# Sheet1.net
KiCad netlist of a schematic drawn in Altium Designer
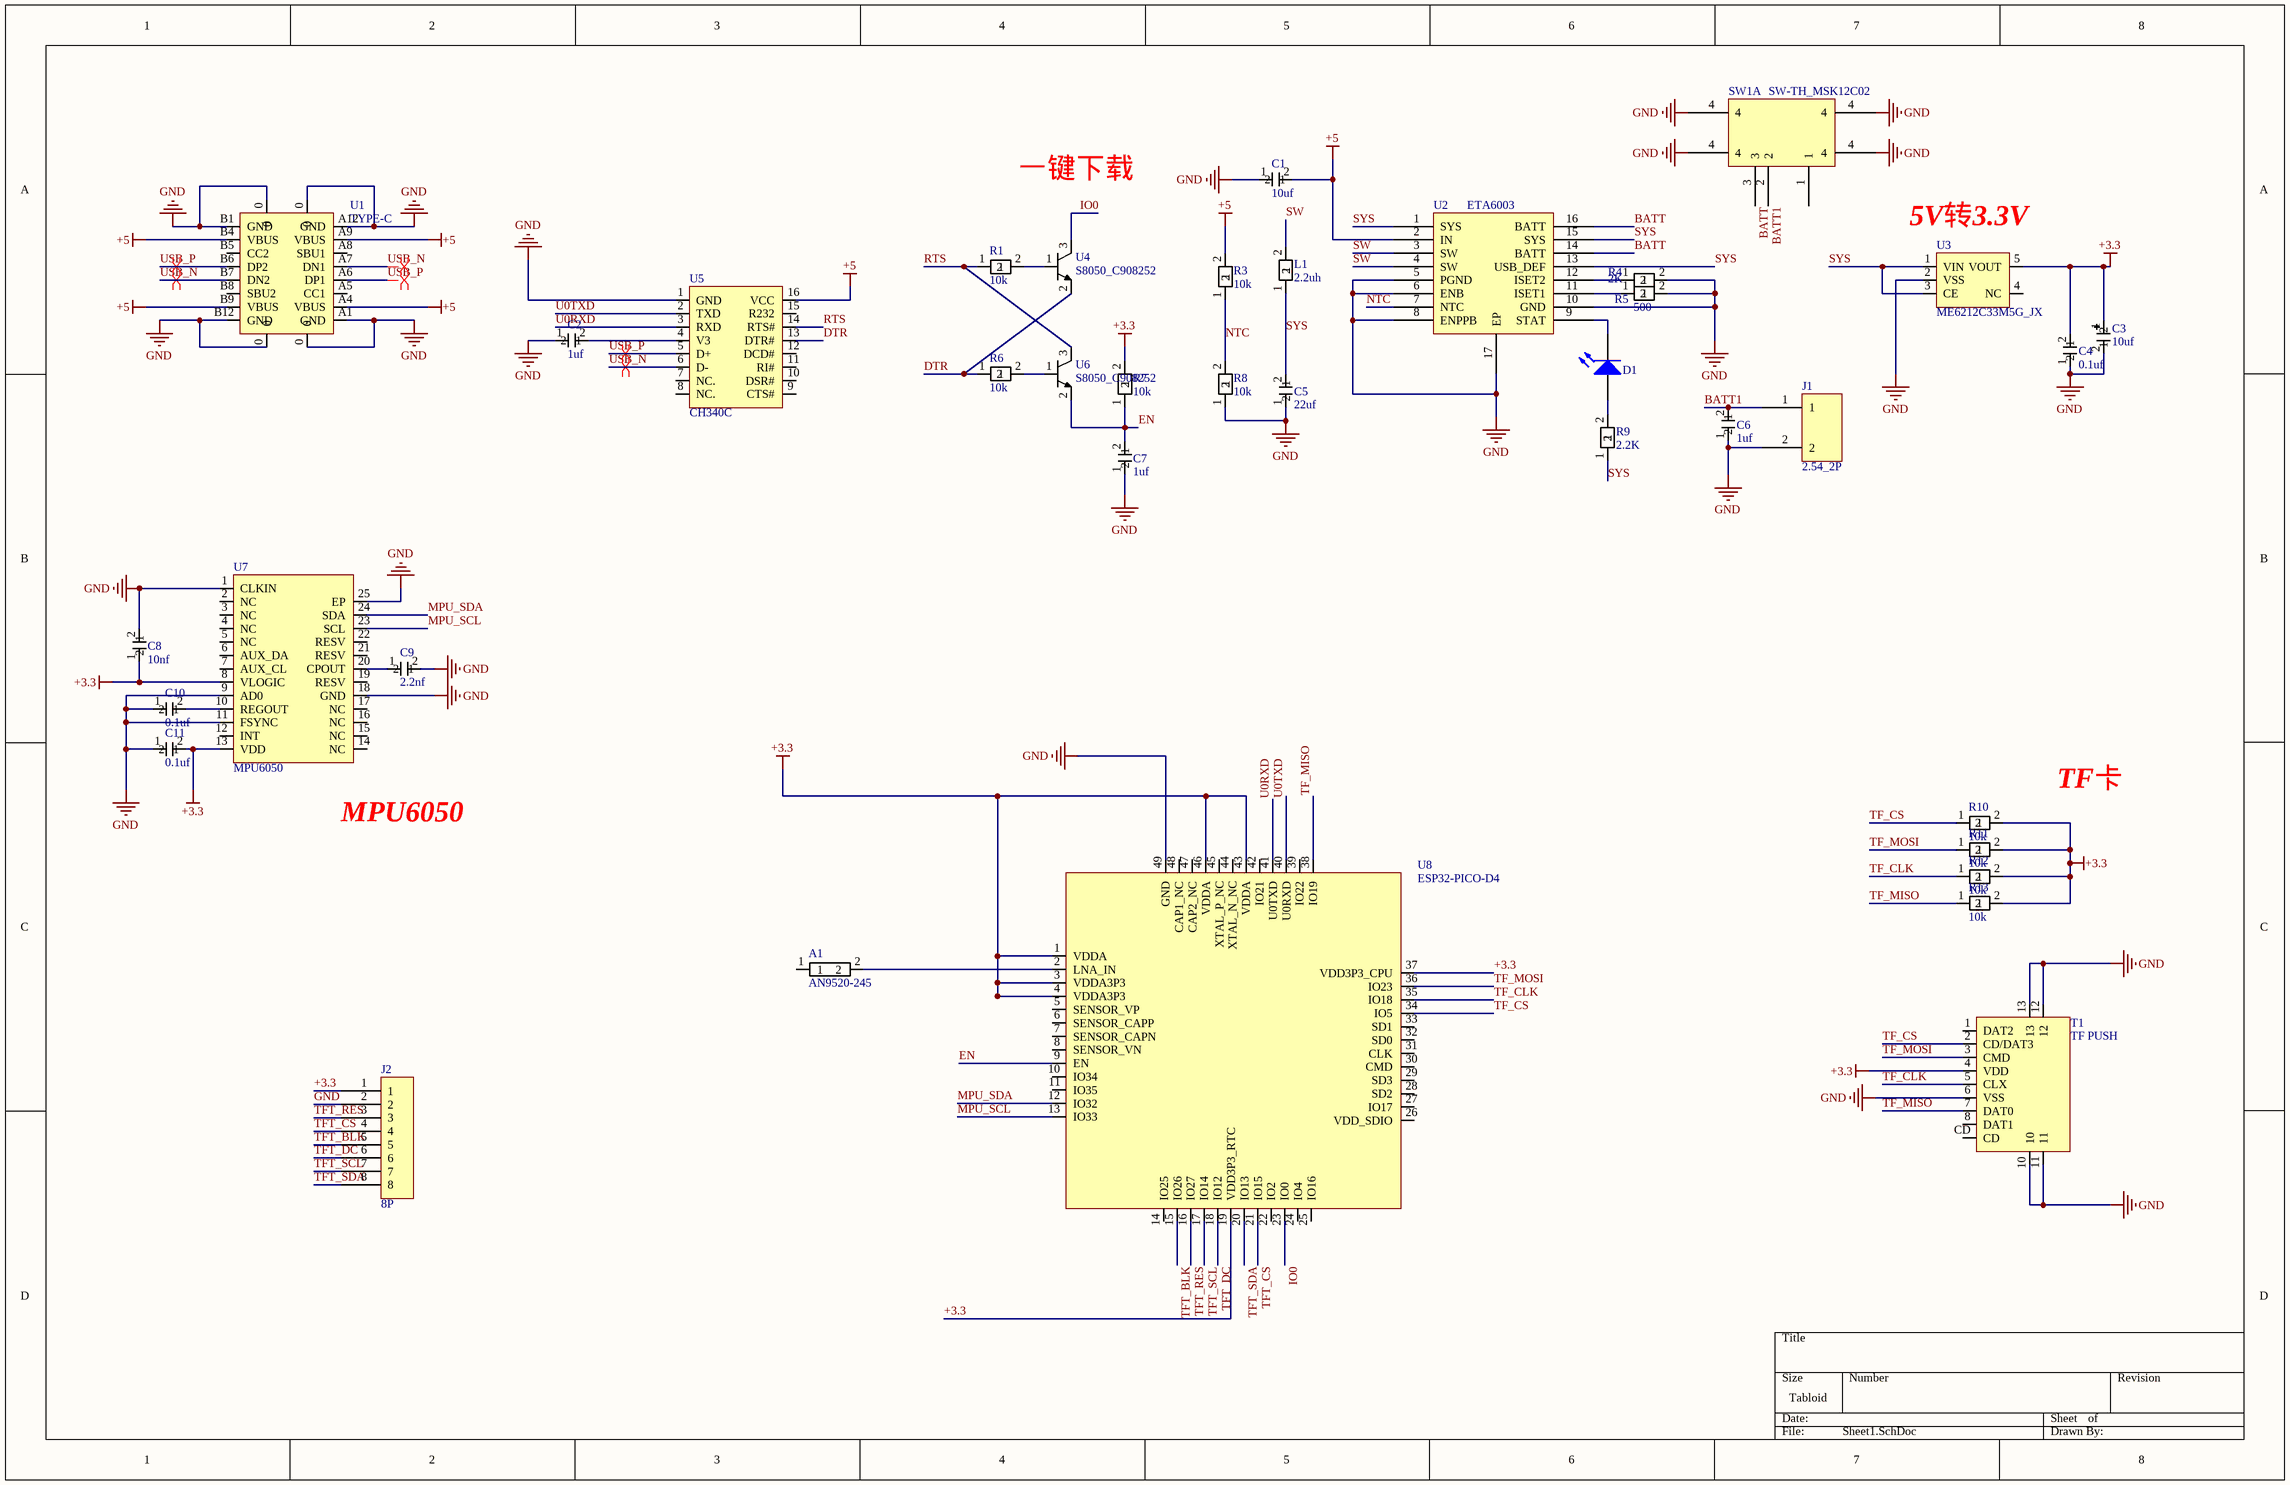
[diagram p0: Sheet1.SchDoc]

(export (version "E")
  (design (tool "Eeschema 10.0.6"))
  (components
    (comp (ref "A1") (value "AN9520-245") (footprint "AN9520-245") (libsource (lib "My") (part "AN9520-245")))
    (comp (ref "C1") (value "10uf") (footprint "C0805") (libsource (lib "My") (part "C0805")))
    (comp (ref "C2") (value "1uf") (footprint "C0805") (libsource (lib "My") (part "C0805")))
    (comp (ref "C3") (value "10uf") (footprint "C+") (libsource (lib "My") (part "C+")))
    (comp (ref "C4") (value "0.1uf") (footprint "C0805") (libsource (lib "My") (part "C0805")))
    (comp (ref "C5") (value "22uf") (footprint "C0805") (libsource (lib "My") (part "C0805")))
    (comp (ref "C6") (value "1uf") (footprint "C0805") (libsource (lib "My") (part "C0805")))
    (comp (ref "C7") (value "1uf") (footprint "C0805") (libsource (lib "My") (part "C0805")))
    (comp (ref "C8") (value "10nf") (footprint "C0805") (libsource (lib "My") (part "C0805")))
    (comp (ref "C9") (value "2.2nf") (footprint "C0805") (libsource (lib "My") (part "C0805")))
    (comp (ref "C10") (value "0.1uf") (footprint "C0805") (libsource (lib "My") (part "C0805")))
    (comp (ref "C11") (value "0.1uf") (footprint "C0805") (libsource (lib "My") (part "C0805")))
    (comp (ref "D1")
      (value "LED 蓝 0805")
      (footprint "LED 蓝  0805")
      (libsource (lib "改好的库") (part "LED 蓝 0805"))
    )
    (comp (ref "J1") (value "2.54_2P") (footprint "2P") (libsource (lib "My") (part "2.54_2P")))
    (comp (ref "J2") (value "8P") (footprint "8P-P2.54") (libsource (lib "My") (part "8P")))
    (comp (ref "L1") (value "2.2uh") (footprint "R0805") (libsource (lib "My") (part "R0805")))
    (comp (ref "R1") (value "10k") (footprint "R0805") (libsource (lib "Schlib1") (part "R0805")))
    (comp (ref "R3") (value "10k") (footprint "R0805") (libsource (lib "My") (part "R0805")))
    (comp (ref "R4") (value "2K") (footprint "R0805") (libsource (lib "My") (part "R0805")))
    (comp (ref "R5") (value "500") (footprint "R0805") (libsource (lib "My") (part "R0805")))
    (comp (ref "R6") (value "10k") (footprint "R0805") (libsource (lib "Schlib1") (part "R0805")))
    (comp (ref "R7") (value "10k") (footprint "R0805") (libsource (lib "Schlib1") (part "R0805")))
    (comp (ref "R8") (value "10k") (footprint "R0805") (libsource (lib "My") (part "R0805")))
    (comp (ref "R9") (value "2.2K") (footprint "R0805") (libsource (lib "My") (part "R0805")))
    (comp (ref "R10") (value "10k") (footprint "R0805") (libsource (lib "Schlib1") (part "R0805")))
    (comp (ref "R11") (value "10k") (footprint "R0805") (libsource (lib "Schlib1") (part "R0805")))
    (comp (ref "R12") (value "10k") (footprint "R0805") (libsource (lib "Schlib1") (part "R0805")))
    (comp (ref "R13") (value "10k") (footprint "R0805") (libsource (lib "Schlib1") (part "R0805")))
    (comp (ref "SW1")
      (value "SW-TH_MSK12C02")
      (footprint "SW-TH_MSK12C02")
      (libsource (lib "My") (part "SW-TH_MSK12C02"))
    )
    (comp (ref "T1") (value "TF PUSH") (footprint "TF-SMD_TF-PUSH") (libsource (lib "My") (part "TF PUSH")))
    (comp (ref "U1")
      (value "TYPE-C")
      (footprint "USB-C")
      (description "TYPE-C-31-M-12")
      (libsource (lib "My") (part "TYPE-C"))
    )
    (comp (ref "U2") (value "ETA6003") (footprint "ETA6003") (libsource (lib "My") (part "ETA6003")))
    (comp (ref "U3")
      (value "ME6212C33M5G_JX")
      (footprint "ME6212C33M5G_JX")
      (libsource (lib "My") (part "ME6212C33M5G_JX"))
    )
    (comp (ref "U4") (value "S8050_C908252") (footprint "s8050") (libsource (lib "My") (part "s8050")))
    (comp (ref "U5") (value "CH340C") (footprint "CH340C") (libsource (lib "My") (part "CH340C")))
    (comp (ref "U6") (value "S8050_C908252") (footprint "s8050") (libsource (lib "My") (part "s8050")))
    (comp (ref "U7") (value "MPU6050") (footprint "MPU6050") (libsource (lib "My") (part "MPU6050")))
    (comp (ref "U8")
      (value "ESP32-PICO-D4")
      (footprint "ESP32-PICO-D4")
      (libsource (lib "My") (part "ESP32-PICO-D4"))
    )
  )
  (nets
    (net (code "1") (name "+3.3") (class "Default")
      (node (ref "C11") (pin "2") (pinfunction "2_2") (pintype "passive"))
      (node (ref "C3") (pin "1") (pinfunction "1_1") (pintype "passive"))
      (node (ref "C4") (pin "2") (pinfunction "2_2") (pintype "passive"))
      (node (ref "C8") (pin "1") (pinfunction "1_1") (pintype "passive"))
      (node (ref "J2") (pin "1") (pinfunction "1_1") (pintype "passive"))
      (node (ref "R10") (pin "2") (pinfunction "2_2") (pintype "passive"))
      (node (ref "R11") (pin "2") (pinfunction "2_2") (pintype "passive"))
      (node (ref "R12") (pin "2") (pinfunction "2_2") (pintype "passive"))
      (node (ref "R13") (pin "2") (pinfunction "2_2") (pintype "passive"))
      (node (ref "R7") (pin "2") (pinfunction "2_2") (pintype "passive"))
      (node (ref "T1") (pin "4") (pinfunction "VDD_4") (pintype "passive"))
      (node (ref "U3") (pin "5") (pinfunction "VOUT_5") (pintype "passive"))
      (node (ref "U7") (pin "13") (pinfunction "VDD_13") (pintype "passive"))
      (node (ref "U7") (pin "8") (pinfunction "VLOGIC_8") (pintype "passive"))
      (node (ref "U8") (pin "1") (pinfunction "VDDA_1") (pintype "passive"))
      (node (ref "U8") (pin "19") (pinfunction "VDD3P3_RTC_19") (pintype "passive"))
      (node (ref "U8") (pin "3") (pinfunction "VDDA3P3_3") (pintype "passive"))
      (node (ref "U8") (pin "37") (pinfunction "VDD3P3_CPU_37") (pintype "passive"))
      (node (ref "U8") (pin "4") (pinfunction "VDDA3P3_4") (pintype "passive"))
      (node (ref "U8") (pin "43") (pinfunction "VDDA_43") (pintype "passive"))
      (node (ref "U8") (pin "46") (pinfunction "VDDA_46") (pintype "passive"))
    )
    (net (code "2") (name "+5") (class "Default")
      (node (ref "C1") (pin "2") (pinfunction "2_2") (pintype "passive"))
      (node (ref "R3") (pin "2") (pinfunction "2_2") (pintype "passive"))
      (node (ref "U1") (pin "A4") (pinfunction "VBUS_A4") (pintype "passive"))
      (node (ref "U1") (pin "A9") (pinfunction "VBUS_A9") (pintype "passive"))
      (node (ref "U1") (pin "B4") (pinfunction "VBUS_B4") (pintype "passive"))
      (node (ref "U1") (pin "B9") (pinfunction "VBUS_B9") (pintype "passive"))
      (node (ref "U2") (pin "2") (pinfunction "IN_2") (pintype "passive"))
      (node (ref "U5") (pin "16") (pinfunction "VCC_16") (pintype "passive"))
    )
    (net (code "4") (name "/BATT") (class "Default")
      (node (ref "SW1") (pin "3") (pinfunction "3_3") (pintype "passive"))
      (node (ref "U2") (pin "14") (pinfunction "BATT_14") (pintype "passive"))
      (node (ref "U2") (pin "16") (pinfunction "BATT_16") (pintype "passive"))
    )
    (net (code "5") (name "/BATT1") (class "Default")
      (node (ref "C6") (pin "2") (pinfunction "2_2") (pintype "passive"))
      (node (ref "J1") (pin "1") (pinfunction "1_1") (pintype "passive"))
      (node (ref "SW1") (pin "2") (pinfunction "2_2") (pintype "passive"))
    )
    (net (code "6") (name "/DTR") (class "Default")
      (node (ref "R6") (pin "1") (pinfunction "1_1") (pintype "passive"))
      (node (ref "U4") (pin "2") (pinfunction "E_2") (pintype "passive"))
      (node (ref "U5") (pin "13") (pinfunction "DTR#_13") (pintype "passive"))
    )
    (net (code "7") (name "/EN") (class "Default")
      (node (ref "C7") (pin "2") (pinfunction "2_2") (pintype "passive"))
      (node (ref "R7") (pin "1") (pinfunction "1_1") (pintype "passive"))
      (node (ref "U6") (pin "2") (pinfunction "E_2") (pintype "passive"))
      (node (ref "U8") (pin "9") (pinfunction "EN_9") (pintype "passive"))
    )
    (net (code "8") (name "/IO0") (class "Default")
      (node (ref "U4") (pin "3") (pinfunction "C_3") (pintype "passive"))
      (node (ref "U8") (pin "23") (pinfunction "IO0_23") (pintype "passive"))
    )
    (net (code "9") (name "/MPU_SCL") (class "Default")
      (node (ref "U7") (pin "23") (pinfunction "SCL_23") (pintype "passive"))
      (node (ref "U8") (pin "13") (pinfunction "IO33_13") (pintype "passive"))
    )
    (net (code "10") (name "/MPU_SDA") (class "Default")
      (node (ref "U7") (pin "24") (pinfunction "SDA_24") (pintype "passive"))
      (node (ref "U8") (pin "12") (pinfunction "IO32_12") (pintype "passive"))
    )
    (net (code "11") (name "/NTC") (class "Default")
      (node (ref "R3") (pin "1") (pinfunction "1_1") (pintype "passive"))
      (node (ref "R8") (pin "2") (pinfunction "2_2") (pintype "passive"))
      (node (ref "U2") (pin "7") (pinfunction "NTC_7") (pintype "passive"))
    )
    (net (code "12") (name "/RTS") (class "Default")
      (node (ref "R1") (pin "1") (pinfunction "1_1") (pintype "passive"))
      (node (ref "U5") (pin "14") (pinfunction "RTS#_14") (pintype "passive"))
      (node (ref "U6") (pin "3") (pinfunction "C_3") (pintype "passive"))
    )
    (net (code "13") (name "/SW") (class "Default")
      (node (ref "L1") (pin "2") (pinfunction "2_2") (pintype "passive"))
      (node (ref "U2") (pin "3") (pinfunction "SW_3") (pintype "passive"))
      (node (ref "U2") (pin "4") (pinfunction "SW_4") (pintype "passive"))
    )
    (net (code "14") (name "/SYS") (class "Default")
      (node (ref "C5") (pin "2") (pinfunction "2_2") (pintype "passive"))
      (node (ref "L1") (pin "1") (pinfunction "1_1") (pintype "passive"))
      (node (ref "R9") (pin "1") (pinfunction "1_1") (pintype "passive"))
      (node (ref "U2") (pin "1") (pinfunction "SYS_1") (pintype "passive"))
      (node (ref "U2") (pin "13") (pinfunction "USB_DEF_13") (pintype "passive"))
      (node (ref "U2") (pin "15") (pinfunction "SYS_15") (pintype "passive"))
      (node (ref "U3") (pin "1") (pinfunction "VIN_1") (pintype "passive"))
      (node (ref "U3") (pin "3") (pinfunction "CE_3") (pintype "passive"))
    )
    (net (code "15") (name "/TFT_BLK") (class "Default")
      (node (ref "J2") (pin "5") (pinfunction "5_5") (pintype "passive"))
      (node (ref "U8") (pin "15") (pinfunction "IO26_15") (pintype "passive"))
    )
    (net (code "16") (name "/TFT_CS") (class "Default")
      (node (ref "J2") (pin "4") (pinfunction "4_4") (pintype "passive"))
      (node (ref "U8") (pin "21") (pinfunction "IO15_21") (pintype "passive"))
    )
    (net (code "17") (name "/TFT_DC") (class "Default")
      (node (ref "J2") (pin "6") (pinfunction "6_6") (pintype "passive"))
      (node (ref "U8") (pin "18") (pinfunction "IO12_18") (pintype "passive"))
    )
    (net (code "18") (name "/TFT_RES") (class "Default")
      (node (ref "J2") (pin "3") (pinfunction "3_3") (pintype "passive"))
      (node (ref "U8") (pin "16") (pinfunction "IO27_16") (pintype "passive"))
    )
    (net (code "19") (name "/TFT_SCL") (class "Default")
      (node (ref "J2") (pin "7") (pinfunction "7_7") (pintype "passive"))
      (node (ref "U8") (pin "17") (pinfunction "IO14_17") (pintype "passive"))
    )
    (net (code "20") (name "/TFT_SDA") (class "Default")
      (node (ref "J2") (pin "8") (pinfunction "8_8") (pintype "passive"))
      (node (ref "U8") (pin "20") (pinfunction "IO13_20") (pintype "passive"))
    )
    (net (code "21") (name "/TF_CLK") (class "Default")
      (node (ref "R12") (pin "1") (pinfunction "1_1") (pintype "passive"))
      (node (ref "T1") (pin "5") (pinfunction "CLX_5") (pintype "passive"))
      (node (ref "U8") (pin "35") (pinfunction "IO18_35") (pintype "passive"))
    )
    (net (code "22") (name "/TF_CS") (class "Default")
      (node (ref "R10") (pin "1") (pinfunction "1_1") (pintype "passive"))
      (node (ref "T1") (pin "2") (pinfunction "CD/DAT3_2") (pintype "passive"))
      (node (ref "U8") (pin "34") (pinfunction "IO5_34") (pintype "passive"))
    )
    (net (code "23") (name "/TF_MISO") (class "Default")
      (node (ref "R13") (pin "1") (pinfunction "1_1") (pintype "passive"))
      (node (ref "T1") (pin "7") (pinfunction "DAT0_7") (pintype "passive"))
      (node (ref "U8") (pin "38") (pinfunction "IO19_38") (pintype "passive"))
    )
    (net (code "24") (name "/TF_MOSI") (class "Default")
      (node (ref "R11") (pin "1") (pinfunction "1_1") (pintype "passive"))
      (node (ref "T1") (pin "3") (pinfunction "CMD_3") (pintype "passive"))
      (node (ref "U8") (pin "36") (pinfunction "IO23_36") (pintype "passive"))
    )
    (net (code "25") (name "/U0RXD") (class "Default")
      (node (ref "U5") (pin "3") (pinfunction "RXD_3") (pintype "passive"))
      (node (ref "U8") (pin "41") (pinfunction "U0TXD_41") (pintype "passive"))
    )
    (net (code "26") (name "/U0TXD") (class "Default")
      (node (ref "U5") (pin "2") (pinfunction "TXD_2") (pintype "passive"))
      (node (ref "U8") (pin "40") (pinfunction "U0RXD_40") (pintype "passive"))
    )
    (net (code "27") (name "/USB_N") (class "Default")
      (node (ref "U1") (pin "A7") (pinfunction "DN1_A7") (pintype "passive"))
      (node (ref "U1") (pin "B7") (pinfunction "DN2_B7") (pintype "passive"))
      (node (ref "U5") (pin "6") (pinfunction "D-_6") (pintype "passive"))
    )
    (net (code "28") (name "/USB_P") (class "Default")
      (node (ref "U1") (pin "A6") (pinfunction "DP1_A6") (pintype "passive"))
      (node (ref "U1") (pin "B6") (pinfunction "DP2_B6") (pintype "passive"))
      (node (ref "U5") (pin "5") (pinfunction "D+_5") (pintype "passive"))
    )
    (net (code "29") (name "GND") (class "Default")
      (node (ref "C1") (pin "1") (pinfunction "1_1") (pintype "passive"))
      (node (ref "C10") (pin "1") (pinfunction "1_1") (pintype "passive"))
      (node (ref "C11") (pin "1") (pinfunction "1_1") (pintype "passive"))
      (node (ref "C2") (pin "1") (pinfunction "1_1") (pintype "passive"))
      (node (ref "C3") (pin "2") (pinfunction "2_2") (pintype "passive"))
      (node (ref "C4") (pin "1") (pinfunction "1_1") (pintype "passive"))
      (node (ref "C5") (pin "1") (pinfunction "1_1") (pintype "passive"))
      (node (ref "C6") (pin "1") (pinfunction "1_1") (pintype "passive"))
      (node (ref "C7") (pin "1") (pinfunction "1_1") (pintype "passive"))
      (node (ref "C8") (pin "2") (pinfunction "2_2") (pintype "passive"))
      (node (ref "C9") (pin "2") (pinfunction "2_2") (pintype "passive"))
      (node (ref "J1") (pin "2") (pinfunction "2_2") (pintype "passive"))
      (node (ref "J2") (pin "2") (pinfunction "2_2") (pintype "passive"))
      (node (ref "R4") (pin "2") (pinfunction "2_2") (pintype "passive"))
      (node (ref "R5") (pin "2") (pinfunction "2_2") (pintype "passive"))
      (node (ref "R8") (pin "1") (pinfunction "1_1") (pintype "passive"))
      (node (ref "SW1") (pin "4") (pinfunction "4_4") (pintype "passive"))
      (node (ref "T1") (pin "10") (pinfunction "10_10") (pintype "passive"))
      (node (ref "T1") (pin "11") (pinfunction "11_11") (pintype "passive"))
      (node (ref "T1") (pin "12") (pinfunction "12_12") (pintype "passive"))
      (node (ref "T1") (pin "13") (pinfunction "13_13") (pintype "passive"))
      (node (ref "T1") (pin "6") (pinfunction "VSS_6") (pintype "passive"))
      (node (ref "U1") (pin "0") (pinfunction "0_0") (pintype "passive"))
      (node (ref "U1") (pin "A1") (pinfunction "GND_A1") (pintype "passive"))
      (node (ref "U1") (pin "A12") (pinfunction "GND_A12") (pintype "passive"))
      (node (ref "U1") (pin "B1") (pinfunction "GND_B1") (pintype "passive"))
      (node (ref "U1") (pin "B12") (pinfunction "GND_B12") (pintype "passive"))
      (node (ref "U2") (pin "10") (pinfunction "GND_10") (pintype "passive"))
      (node (ref "U2") (pin "17") (pinfunction "EP_17") (pintype "passive"))
      (node (ref "U2") (pin "5") (pinfunction "PGND_5") (pintype "passive"))
      (node (ref "U2") (pin "6") (pinfunction "ENB_6") (pintype "passive"))
      (node (ref "U2") (pin "8") (pinfunction "ENPPB_8") (pintype "passive"))
      (node (ref "U3") (pin "2") (pinfunction "VSS_2") (pintype "passive"))
      (node (ref "U5") (pin "1") (pinfunction "GND_1") (pintype "passive"))
      (node (ref "U7") (pin "1") (pinfunction "CLKIN_1") (pintype "passive"))
      (node (ref "U7") (pin "11") (pinfunction "FSYNC_11") (pintype "passive"))
      (node (ref "U7") (pin "18") (pinfunction "GND_18") (pintype "passive"))
      (node (ref "U7") (pin "25") (pinfunction "EP_25") (pintype "passive"))
      (node (ref "U7") (pin "9") (pinfunction "AD0_9") (pintype "passive"))
      (node (ref "U8") (pin "49") (pinfunction "GND_49") (pintype "passive"))
    )
    (net (code "30") (name "Net-(D1-A)") (class "Default")
      (node (ref "D1") (pin "1") (pinfunction "A_1") (pintype "passive"))
      (node (ref "R9") (pin "2") (pinfunction "2_2") (pintype "passive"))
    )
    (net (code "31") (name "Net-(D1-K)") (class "Default")
      (node (ref "D1") (pin "2") (pinfunction "K_2") (pintype "passive"))
      (node (ref "U2") (pin "9") (pinfunction "STAT_9") (pintype "passive"))
    )
    (net (code "32") (name "Net-(U2-ISET1)") (class "Default")
      (node (ref "R5") (pin "1") (pinfunction "1_1") (pintype "passive"))
      (node (ref "U2") (pin "11") (pinfunction "ISET1_11") (pintype "passive"))
    )
    (net (code "33") (name "Net-(U2-ISET2)") (class "Default")
      (node (ref "R4") (pin "1") (pinfunction "1_1") (pintype "passive"))
      (node (ref "U2") (pin "12") (pinfunction "ISET2_12") (pintype "passive"))
    )
    (net (code "34") (name "Net-(U4-B)") (class "Default")
      (node (ref "R1") (pin "2") (pinfunction "2_2") (pintype "passive"))
      (node (ref "U4") (pin "1") (pinfunction "B_1") (pintype "passive"))
    )
    (net (code "35") (name "Net-(U5-V3)") (class "Default")
      (node (ref "C2") (pin "2") (pinfunction "2_2") (pintype "passive"))
      (node (ref "U5") (pin "4") (pinfunction "V3_4") (pintype "passive"))
    )
    (net (code "36") (name "Net-(U6-B)") (class "Default")
      (node (ref "R6") (pin "2") (pinfunction "2_2") (pintype "passive"))
      (node (ref "U6") (pin "1") (pinfunction "B_1") (pintype "passive"))
    )
    (net (code "37") (name "Net-(U7-CPOUT)") (class "Default")
      (node (ref "C9") (pin "1") (pinfunction "1_1") (pintype "passive"))
      (node (ref "U7") (pin "20") (pinfunction "CPOUT_20") (pintype "passive"))
    )
    (net (code "38") (name "Net-(U7-REGOUT)") (class "Default")
      (node (ref "C10") (pin "2") (pinfunction "2_2") (pintype "passive"))
      (node (ref "U7") (pin "10") (pinfunction "REGOUT_10") (pintype "passive"))
    )
    (net (code "39") (name "Net-(U8-LNA_IN)") (class "Default")
      (node (ref "A1") (pin "2") (pinfunction "2_2") (pintype "passive"))
      (node (ref "U8") (pin "2") (pinfunction "LNA_IN_2") (pintype "passive"))
    )
    (net (code "40") (name "unconnected-(A1-Pad1)") (class "Default")
      (node (ref "A1") (pin "1") (pinfunction "1_1") (pintype "passive"))
    )
    (net (code "41") (name "unconnected-(SW1-Pad1)") (class "Default")
      (node (ref "SW1") (pin "1") (pinfunction "1_1") (pintype "passive"))
    )
    (net (code "42") (name "unconnected-(T1-DAT1-Pad8)") (class "Default")
      (node (ref "T1") (pin "8") (pinfunction "DAT1_8") (pintype "passive"))
    )
    (net (code "43") (name "unconnected-(T1-DAT2-Pad1)") (class "Default")
      (node (ref "T1") (pin "1") (pinfunction "DAT2_1") (pintype "passive"))
    )
    (net (code "44") (name "unconnected-(T1-PadCD)") (class "Default")
      (node (ref "T1") (pin "CD") (pinfunction "CD_CD") (pintype "passive"))
    )
    (net (code "45") (name "unconnected-(U1-CC1-PadA5)") (class "Default")
      (node (ref "U1") (pin "A5") (pinfunction "CC1_A5") (pintype "passive"))
    )
    (net (code "46") (name "unconnected-(U1-CC2-PadB5)") (class "Default")
      (node (ref "U1") (pin "B5") (pinfunction "CC2_B5") (pintype "passive"))
    )
    (net (code "47") (name "unconnected-(U1-SBU1-PadA8)") (class "Default")
      (node (ref "U1") (pin "A8") (pinfunction "SBU1_A8") (pintype "passive"))
    )
    (net (code "48") (name "unconnected-(U1-SBU2-PadB8)") (class "Default")
      (node (ref "U1") (pin "B8") (pinfunction "SBU2_B8") (pintype "passive"))
    )
    (net (code "49") (name "unconnected-(U3-NC-Pad4)") (class "Default")
      (node (ref "U3") (pin "4") (pinfunction "NC_4") (pintype "passive"))
    )
    (net (code "50") (name "unconnected-(U5-CTS#-Pad9)") (class "Default")
      (node (ref "U5") (pin "9") (pinfunction "CTS#_9") (pintype "passive"))
    )
    (net (code "51") (name "unconnected-(U5-DCD#-Pad12)") (class "Default")
      (node (ref "U5") (pin "12") (pinfunction "DCD#_12") (pintype "passive"))
    )
    (net (code "52") (name "unconnected-(U5-DSR#-Pad10)") (class "Default")
      (node (ref "U5") (pin "10") (pinfunction "DSR#_10") (pintype "passive"))
    )
    (net (code "53") (name "unconnected-(U5-NC.-Pad7)") (class "Default")
      (node (ref "U5") (pin "7") (pinfunction "NC._7") (pintype "passive"))
    )
    (net (code "54") (name "unconnected-(U5-NC.-Pad8)") (class "Default")
      (node (ref "U5") (pin "8") (pinfunction "NC._8") (pintype "passive"))
    )
    (net (code "55") (name "unconnected-(U5-R232-Pad15)") (class "Default")
      (node (ref "U5") (pin "15") (pinfunction "R232_15") (pintype "passive"))
    )
    (net (code "56") (name "unconnected-(U5-RI#-Pad11)") (class "Default")
      (node (ref "U5") (pin "11") (pinfunction "RI#_11") (pintype "passive"))
    )
    (net (code "57") (name "unconnected-(U7-AUX_CL-Pad7)") (class "Default")
      (node (ref "U7") (pin "7") (pinfunction "AUX_CL_7") (pintype "passive"))
    )
    (net (code "58") (name "unconnected-(U7-AUX_DA-Pad6)") (class "Default")
      (node (ref "U7") (pin "6") (pinfunction "AUX_DA_6") (pintype "passive"))
    )
    (net (code "59") (name "unconnected-(U7-INT-Pad12)") (class "Default")
      (node (ref "U7") (pin "12") (pinfunction "INT_12") (pintype "passive"))
    )
    (net (code "60") (name "unconnected-(U7-NC-Pad2)") (class "Default")
      (node (ref "U7") (pin "2") (pinfunction "NC_2") (pintype "passive"))
    )
    (net (code "61") (name "unconnected-(U7-NC-Pad3)") (class "Default")
      (node (ref "U7") (pin "3") (pinfunction "NC_3") (pintype "passive"))
    )
    (net (code "62") (name "unconnected-(U7-NC-Pad4)") (class "Default")
      (node (ref "U7") (pin "4") (pinfunction "NC_4") (pintype "passive"))
    )
    (net (code "63") (name "unconnected-(U7-NC-Pad5)") (class "Default")
      (node (ref "U7") (pin "5") (pinfunction "NC_5") (pintype "passive"))
    )
    (net (code "64") (name "unconnected-(U7-NC-Pad14)") (class "Default")
      (node (ref "U7") (pin "14") (pinfunction "NC_14") (pintype "passive"))
    )
    (net (code "65") (name "unconnected-(U7-NC-Pad15)") (class "Default")
      (node (ref "U7") (pin "15") (pinfunction "NC_15") (pintype "passive"))
    )
    (net (code "66") (name "unconnected-(U7-NC-Pad16)") (class "Default")
      (node (ref "U7") (pin "16") (pinfunction "NC_16") (pintype "passive"))
    )
    (net (code "67") (name "unconnected-(U7-NC-Pad17)") (class "Default")
      (node (ref "U7") (pin "17") (pinfunction "NC_17") (pintype "passive"))
    )
    (net (code "68") (name "unconnected-(U7-RESV-Pad19)") (class "Default")
      (node (ref "U7") (pin "19") (pinfunction "RESV_19") (pintype "passive"))
    )
    (net (code "69") (name "unconnected-(U7-RESV-Pad21)") (class "Default")
      (node (ref "U7") (pin "21") (pinfunction "RESV_21") (pintype "passive"))
    )
    (net (code "70") (name "unconnected-(U7-RESV-Pad22)") (class "Default")
      (node (ref "U7") (pin "22") (pinfunction "RESV_22") (pintype "passive"))
    )
    (net (code "71") (name "unconnected-(U8-CAP1_NC-Pad48)") (class "Default")
      (node (ref "U8") (pin "48") (pinfunction "CAP1_NC_48") (pintype "passive"))
    )
    (net (code "72") (name "unconnected-(U8-CAP2_NC-Pad47)") (class "Default")
      (node (ref "U8") (pin "47") (pinfunction "CAP2_NC_47") (pintype "passive"))
    )
    (net (code "73") (name "unconnected-(U8-CLK-Pad31)") (class "Default")
      (node (ref "U8") (pin "31") (pinfunction "CLK_31") (pintype "passive"))
    )
    (net (code "74") (name "unconnected-(U8-CMD-Pad30)") (class "Default")
      (node (ref "U8") (pin "30") (pinfunction "CMD_30") (pintype "passive"))
    )
    (net (code "75") (name "unconnected-(U8-IO2-Pad22)") (class "Default")
      (node (ref "U8") (pin "22") (pinfunction "IO2_22") (pintype "passive"))
    )
    (net (code "76") (name "unconnected-(U8-IO4-Pad24)") (class "Default")
      (node (ref "U8") (pin "24") (pinfunction "IO4_24") (pintype "passive"))
    )
    (net (code "77") (name "unconnected-(U8-IO16-Pad25)") (class "Default")
      (node (ref "U8") (pin "25") (pinfunction "IO16_25") (pintype "passive"))
    )
    (net (code "78") (name "unconnected-(U8-IO17-Pad27)") (class "Default")
      (node (ref "U8") (pin "27") (pinfunction "IO17_27") (pintype "passive"))
    )
    (net (code "79") (name "unconnected-(U8-IO21-Pad42)") (class "Default")
      (node (ref "U8") (pin "42") (pinfunction "IO21_42") (pintype "passive"))
    )
    (net (code "80") (name "unconnected-(U8-IO22-Pad39)") (class "Default")
      (node (ref "U8") (pin "39") (pinfunction "IO22_39") (pintype "passive"))
    )
    (net (code "81") (name "unconnected-(U8-IO25-Pad14)") (class "Default")
      (node (ref "U8") (pin "14") (pinfunction "IO25_14") (pintype "passive"))
    )
    (net (code "82") (name "unconnected-(U8-IO34-Pad10)") (class "Default")
      (node (ref "U8") (pin "10") (pinfunction "IO34_10") (pintype "passive"))
    )
    (net (code "83") (name "unconnected-(U8-IO35-Pad11)") (class "Default")
      (node (ref "U8") (pin "11") (pinfunction "IO35_11") (pintype "passive"))
    )
    (net (code "84") (name "unconnected-(U8-SD0-Pad32)") (class "Default")
      (node (ref "U8") (pin "32") (pinfunction "SD0_32") (pintype "passive"))
    )
    (net (code "85") (name "unconnected-(U8-SD1-Pad33)") (class "Default")
      (node (ref "U8") (pin "33") (pinfunction "SD1_33") (pintype "passive"))
    )
    (net (code "86") (name "unconnected-(U8-SD2-Pad28)") (class "Default")
      (node (ref "U8") (pin "28") (pinfunction "SD2_28") (pintype "passive"))
    )
    (net (code "87") (name "unconnected-(U8-SD3-Pad29)") (class "Default")
      (node (ref "U8") (pin "29") (pinfunction "SD3_29") (pintype "passive"))
    )
    (net (code "88") (name "unconnected-(U8-SENSOR_CAPN-Pad7)") (class "Default")
      (node (ref "U8") (pin "7") (pinfunction "SENSOR_CAPN_7") (pintype "passive"))
    )
    (net (code "89") (name "unconnected-(U8-SENSOR_CAPP-Pad6)") (class "Default")
      (node (ref "U8") (pin "6") (pinfunction "SENSOR_CAPP_6") (pintype "passive"))
    )
    (net (code "90") (name "unconnected-(U8-SENSOR_VN-Pad8)") (class "Default")
      (node (ref "U8") (pin "8") (pinfunction "SENSOR_VN_8") (pintype "passive"))
    )
    (net (code "91") (name "unconnected-(U8-SENSOR_VP-Pad5)") (class "Default")
      (node (ref "U8") (pin "5") (pinfunction "SENSOR_VP_5") (pintype "passive"))
    )
    (net (code "92") (name "unconnected-(U8-VDD_SDIO-Pad26)") (class "Default")
      (node (ref "U8") (pin "26") (pinfunction "VDD_SDIO_26") (pintype "passive"))
    )
    (net (code "93") (name "unconnected-(U8-XTAL_N_NC-Pad44)") (class "Default")
      (node (ref "U8") (pin "44") (pinfunction "XTAL_N_NC_44") (pintype "passive"))
    )
    (net (code "94") (name "unconnected-(U8-XTAL_P_NC-Pad45)") (class "Default")
      (node (ref "U8") (pin "45") (pinfunction "XTAL_P_NC_45") (pintype "passive"))
    )
  )
)
